# And_gate_using_Transistor.net
KiCad netlist of a schematic drawn in EAGLE
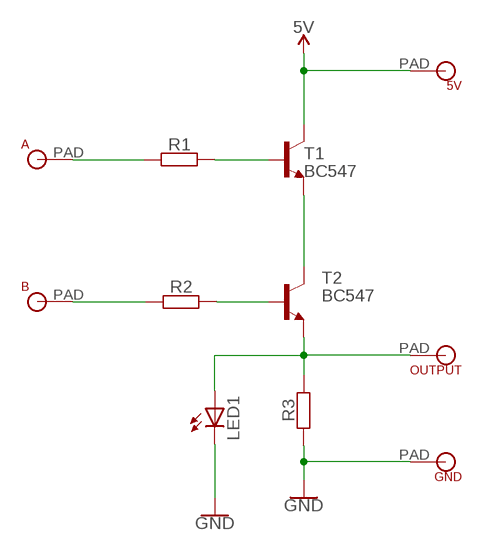
[diagram p0: schematic, sheet 1]

(export (version "E")
  (design (tool "Eeschema 10.0.6"))
  (components
    (comp (ref "5V")
      (value "MICROBIT_PAD")
      (footprint "eagle-import:MICROBIT_PAD")
      (libsource (lib "eagle-import") (part "MICROBIT_PAD"))
    )
    (comp (ref "A")
      (value "MICROBIT_PAD")
      (footprint "eagle-import:MICROBIT_PAD")
      (libsource (lib "eagle-import") (part "MICROBIT_PAD"))
    )
    (comp (ref "B")
      (value "MICROBIT_PAD")
      (footprint "eagle-import:MICROBIT_PAD")
      (libsource (lib "eagle-import") (part "MICROBIT_PAD"))
    )
    (comp (ref "GND")
      (value "MICROBIT_PAD")
      (footprint "eagle-import:MICROBIT_PAD")
      (libsource (lib "eagle-import") (part "MICROBIT_PAD"))
    )
    (comp (ref "LED1")
      (value "LED3MM")
      (footprint "eagle-import:LED3MM")
      (libsource (lib "eagle-import") (part "LED3MM"))
    )
    (comp (ref "OUTPUT")
      (value "MICROBIT_PAD")
      (footprint "eagle-import:MICROBIT_PAD")
      (libsource (lib "eagle-import") (part "MICROBIT_PAD"))
    )
    (comp (ref "R1")
      (value "RESISTOR-07")
      (footprint "eagle-import:R0207_7")
      (libsource (lib "eagle-import") (part "RESISTOR-07"))
    )
    (comp (ref "R2")
      (value "RESISTOR-07")
      (footprint "eagle-import:R0207_7")
      (libsource (lib "eagle-import") (part "RESISTOR-07"))
    )
    (comp (ref "R3")
      (value "RESISTOR-07")
      (footprint "eagle-import:R0207_7")
      (libsource (lib "eagle-import") (part "RESISTOR-07"))
    )
    (comp (ref "T1")
      (value "BC547")
      (footprint "eagle-import:TO92")
      (libsource (lib "eagle-import") (part "BC547"))
    )
    (comp (ref "T2")
      (value "BC547")
      (footprint "eagle-import:TO92")
      (libsource (lib "eagle-import") (part "BC547"))
    )
  )
  (nets
    (net (code "1") (name "5V") (class "Default")
      (node (ref "5V") (pin "PAD") (pinfunction "P$1_PAD") (pintype "bidirectional"))
      (node (ref "T1") (pin "3") (pinfunction "C_3") (pintype "passive"))
    )
    (net (code "2") (name "GND") (class "Default")
      (node (ref "GND") (pin "PAD") (pinfunction "P$1_PAD") (pintype "bidirectional"))
      (node (ref "LED1") (pin "K") (pinfunction "C_K") (pintype "passive"))
      (node (ref "R3") (pin "1") (pinfunction "1_1") (pintype "passive"))
    )
    (net (code "3") (name "Net-(A-P$1)") (class "Default")
      (node (ref "A") (pin "PAD") (pinfunction "P$1_PAD") (pintype "bidirectional"))
      (node (ref "R1") (pin "1") (pinfunction "1_1") (pintype "passive"))
    )
    (net (code "4") (name "Net-(B-P$1)") (class "Default")
      (node (ref "B") (pin "PAD") (pinfunction "P$1_PAD") (pintype "bidirectional"))
      (node (ref "R2") (pin "1") (pinfunction "1_1") (pintype "passive"))
    )
    (net (code "5") (name "Net-(OUTPUT-P$1)") (class "Default")
      (node (ref "LED1") (pin "A") (pinfunction "A_A") (pintype "passive"))
      (node (ref "OUTPUT") (pin "PAD") (pinfunction "P$1_PAD") (pintype "bidirectional"))
      (node (ref "R3") (pin "2") (pinfunction "2_2") (pintype "passive"))
      (node (ref "T2") (pin "1") (pinfunction "E_1") (pintype "passive"))
    )
    (net (code "6") (name "Net-(T1-B)") (class "Default")
      (node (ref "R1") (pin "2") (pinfunction "2_2") (pintype "passive"))
      (node (ref "T1") (pin "2") (pinfunction "B_2") (pintype "passive"))
    )
    (net (code "7") (name "Net-(T1-E)") (class "Default")
      (node (ref "T1") (pin "1") (pinfunction "E_1") (pintype "passive"))
      (node (ref "T2") (pin "3") (pinfunction "C_3") (pintype "passive"))
    )
    (net (code "8") (name "Net-(T2-B)") (class "Default")
      (node (ref "R2") (pin "2") (pinfunction "2_2") (pintype "passive"))
      (node (ref "T2") (pin "2") (pinfunction "B_2") (pintype "passive"))
    )
  )
)
